# testing.net
KiCad netlist of a schematic drawn in Altium Designer
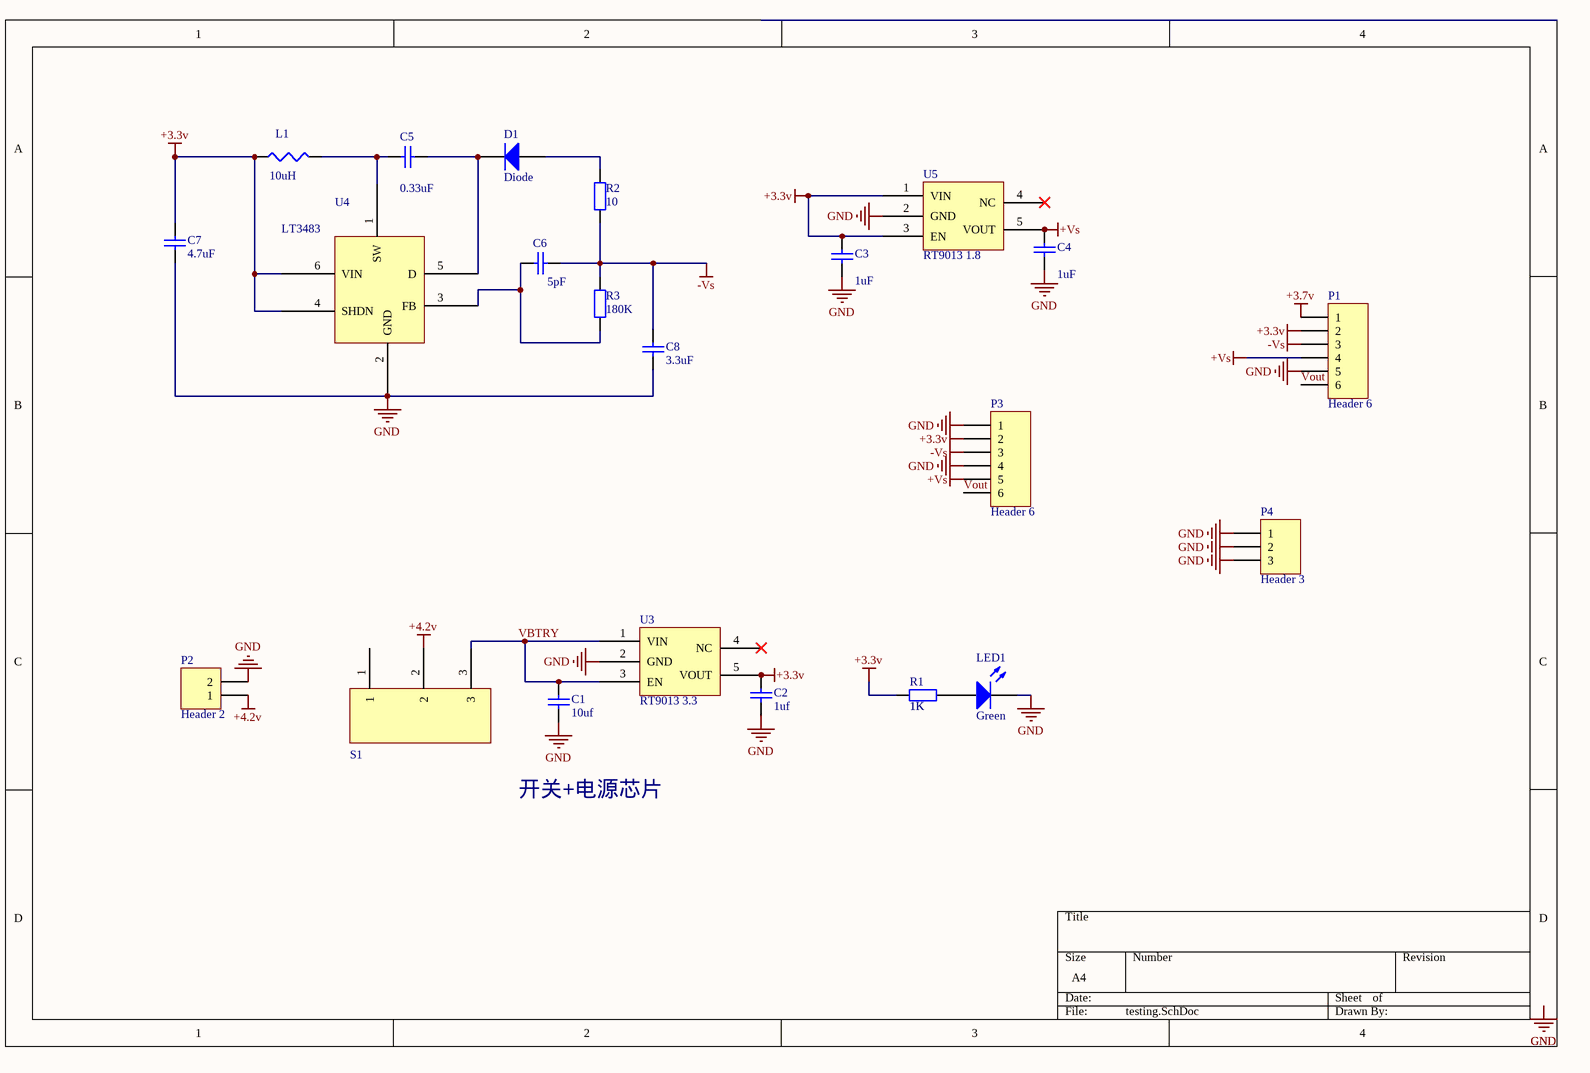
[diagram p0: testing.SchDoc]

(export (version "E")
  (design (tool "Eeschema 10.0.6"))
  (components
    (comp (ref "C1")
      (value "10uf")
      (footprint "0805")
      (description "Capacitor")
      (fields (field (name "PUBLISHER") "Altium Limited"))
      (libsource (lib "Miscellaneous Devices") (part "Cap"))
    )
    (comp (ref "C2")
      (value "1uf")
      (footprint "0805")
      (description "Capacitor")
      (fields (field (name "PUBLISHER") "Altium Limited"))
      (libsource (lib "Miscellaneous Devices") (part "Cap"))
    )
    (comp (ref "C3")
      (value "1uF")
      (footprint "0805")
      (description "Capacitor")
      (fields (field (name "PUBLISHER") "Altium Limited"))
      (libsource (lib "Miscellaneous Devices") (part "Cap"))
    )
    (comp (ref "C4")
      (value "1uF")
      (footprint "0805")
      (description "Capacitor")
      (fields (field (name "PUBLISHER") "Altium Limited"))
      (libsource (lib "Miscellaneous Devices") (part "Cap"))
    )
    (comp (ref "C5")
      (value "0.33uF")
      (footprint "0805")
      (description "Capacitor (Semiconductor SIM Model)")
      (fields (field (name "Comment") "Cap Semi") (field (name "PUBLISHER") "Altium Limited"))
      (libsource (lib "Miscellaneous Devices") (part "Cap Semi"))
    )
    (comp (ref "C6")
      (value "5pF")
      (footprint "0805")
      (description "Capacitor (Semiconductor SIM Model)")
      (fields (field (name "Comment") "Cap Semi") (field (name "PUBLISHER") "Altium Limited"))
      (libsource (lib "Miscellaneous Devices") (part "Cap Semi"))
    )
    (comp (ref "C7")
      (value "4.7uF")
      (footprint "0805")
      (description "Capacitor (Semiconductor SIM Model)")
      (fields (field (name "Comment") "Cap Semi") (field (name "PUBLISHER") "Altium Limited"))
      (libsource (lib "Miscellaneous Devices") (part "Cap Semi"))
    )
    (comp (ref "C8")
      (value "3.3uF")
      (footprint "0805")
      (description "Capacitor (Semiconductor SIM Model)")
      (fields (field (name "Comment") "Cap Semi") (field (name "PUBLISHER") "Altium Limited"))
      (libsource (lib "Miscellaneous Devices") (part "Cap Semi"))
    )
    (comp (ref "D1")
      (value "Diode")
      (footprint "D0402")
      (description "Default Diode")
      (fields (field (name "PUBLISHER") "Altium Limited"))
      (libsource (lib "Miscellaneous Devices") (part "Diode"))
    )
    (comp (ref "L1")
      (value "10uH")
      (footprint "0402 - MI")
      (description "Resistor")
      (fields (field (name "Comment") "Res3") (field (name "PUBLISHER") "Altium Limited"))
      (libsource (lib "Miscellaneous Devices") (part "Res3"))
    )
    (comp (ref "LED1")
      (value "Green")
      (footprint "0805")
      (description "Typical INFRARED GaAs LED")
      (fields (field (name "PUBLISHER") "Altium Limited"))
      (libsource (lib "Miscellaneous Devices") (part "LED0"))
    )
    (comp (ref "P1")
      (value "Header 6")
      (footprint "6P_0.5mm(FPC) - duplicate - duplicate")
      (description "Header, 6-Pin")
      (fields (field (name "PUBLISHER") "Altium Limited"))
      (libsource (lib "Miscellaneous Connectors") (part "Header 6"))
    )
    (comp (ref "P2")
      (value "Header 2")
      (footprint "HDR1X2")
      (description "Header, 2-Pin")
      (fields (field (name "PUBLISHER") "Altium Limited"))
      (libsource (lib "Miscellaneous Connectors") (part "Header 2"))
    )
    (comp (ref "P3")
      (value "Header 6")
      (footprint "HDR1X6")
      (description "Header, 6-Pin")
      (fields (field (name "PUBLISHER") "Altium Limited"))
      (libsource (lib "Miscellaneous Connectors") (part "Header 6"))
    )
    (comp (ref "P4")
      (value "Header 3")
      (footprint "HDR1X3")
      (description "Header, 3-Pin")
      (fields (field (name "PUBLISHER") "Altium Limited"))
      (libsource (lib "Miscellaneous Connectors") (part "Header 3"))
    )
    (comp (ref "R1")
      (value "1K")
      (footprint "0805")
      (description "Resistor")
      (fields (field (name "ALTIUM_VALUE") "1K") (field (name "PUBLISHER") "Altium Limited"))
      (libsource (lib "") (part "Res2_1"))
    )
    (comp (ref "R2")
      (value "10")
      (footprint "0805")
      (description "Resistor")
      (fields (field (name "PUBLISHER") "Altium Limited"))
      (libsource (lib "Miscellaneous Devices") (part "Res2"))
    )
    (comp (ref "R3")
      (value "180K")
      (footprint "0805")
      (description "Resistor")
      (fields (field (name "PUBLISHER") "Altium Limited"))
      (libsource (lib "Miscellaneous Devices") (part "Res2"))
    )
    (comp (ref "S1") (value "~") (footprint "HDR1X3") (libsource (lib "Accelerometer") (part "Switch")))
    (comp (ref "U3")
      (value "RT9013 3.3")
      (footprint "SOT23-5AM")
      (libsource (lib "CC254xPM") (part "RT9013 SOT235"))
    )
    (comp (ref "U4") (value "LT3483") (footprint "LT3843") (libsource (lib "controler") (part "LT3483")))
    (comp (ref "U5")
      (value "RT9013 1.8")
      (footprint "SC-70-5")
      (libsource (lib "CC254xPM") (part "RT9013 SOT235"))
    )
  )
  (nets
    (net (code "1") (name "+3.3v") (class "Default")
      (node (ref "C2") (pin "2") (pinfunction "2_2") (pintype "passive"))
      (node (ref "C3") (pin "2") (pinfunction "2_2") (pintype "passive"))
      (node (ref "C7") (pin "2") (pinfunction "2_2") (pintype "passive"))
      (node (ref "L1") (pin "1") (pinfunction "1_1") (pintype "passive"))
      (node (ref "P1") (pin "2") (pinfunction "2_2") (pintype "passive"))
      (node (ref "P3") (pin "2") (pinfunction "2_2") (pintype "passive"))
      (node (ref "R1") (pin "1") (pinfunction "1_1") (pintype "passive"))
      (node (ref "U3") (pin "5") (pinfunction "VOUT_5") (pintype "passive"))
      (node (ref "U4") (pin "4") (pinfunction "SHDN_4") (pintype "passive"))
      (node (ref "U4") (pin "6") (pinfunction "VIN_6") (pintype "passive"))
      (node (ref "U5") (pin "1") (pinfunction "VIN_1") (pintype "passive"))
      (node (ref "U5") (pin "3") (pinfunction "EN_3") (pintype "passive"))
    )
    (net (code "2") (name "+3.7v") (class "Default")
      (node (ref "P1") (pin "1") (pinfunction "1_1") (pintype "passive"))
    )
    (net (code "3") (name "+4.2v") (class "Default")
      (node (ref "P2") (pin "1") (pinfunction "1_1") (pintype "passive"))
      (node (ref "S1") (pin "2") (pinfunction "2_2") (pintype "passive"))
    )
    (net (code "4") (name "+Vs") (class "Default")
      (node (ref "C4") (pin "2") (pinfunction "2_2") (pintype "passive"))
      (node (ref "P1") (pin "4") (pinfunction "4_4") (pintype "passive"))
      (node (ref "P3") (pin "5") (pinfunction "5_5") (pintype "passive"))
      (node (ref "U5") (pin "5") (pinfunction "VOUT_5") (pintype "passive"))
    )
    (net (code "5") (name "-Vs") (class "Default")
      (node (ref "C6") (pin "2") (pinfunction "2_2") (pintype "passive"))
      (node (ref "C8") (pin "1") (pinfunction "1_1") (pintype "passive"))
      (node (ref "P1") (pin "3") (pinfunction "3_3") (pintype "passive"))
      (node (ref "P3") (pin "3") (pinfunction "3_3") (pintype "passive"))
      (node (ref "R2") (pin "2") (pinfunction "2_2") (pintype "passive"))
      (node (ref "R3") (pin "1") (pinfunction "1_1") (pintype "passive"))
    )
    (net (code "6") (name "/VBTRY") (class "Default")
      (node (ref "C1") (pin "2") (pinfunction "2_2") (pintype "passive"))
      (node (ref "S1") (pin "3") (pinfunction "3_3") (pintype "passive"))
      (node (ref "U3") (pin "1") (pinfunction "VIN_1") (pintype "passive"))
      (node (ref "U3") (pin "3") (pinfunction "EN_3") (pintype "passive"))
    )
    (net (code "7") (name "/Vout") (class "Default")
      (node (ref "P1") (pin "6") (pinfunction "6_6") (pintype "passive"))
      (node (ref "P3") (pin "6") (pinfunction "6_6") (pintype "passive"))
    )
    (net (code "8") (name "GND") (class "Default")
      (node (ref "C1") (pin "1") (pinfunction "1_1") (pintype "passive"))
      (node (ref "C2") (pin "1") (pinfunction "1_1") (pintype "passive"))
      (node (ref "C3") (pin "1") (pinfunction "1_1") (pintype "passive"))
      (node (ref "C4") (pin "1") (pinfunction "1_1") (pintype "passive"))
      (node (ref "C7") (pin "1") (pinfunction "1_1") (pintype "passive"))
      (node (ref "C8") (pin "2") (pinfunction "2_2") (pintype "passive"))
      (node (ref "LED1") (pin "2") (pinfunction "K_2") (pintype "passive"))
      (node (ref "P1") (pin "5") (pinfunction "5_5") (pintype "passive"))
      (node (ref "P2") (pin "2") (pinfunction "2_2") (pintype "passive"))
      (node (ref "P3") (pin "1") (pinfunction "1_1") (pintype "passive"))
      (node (ref "P3") (pin "4") (pinfunction "4_4") (pintype "passive"))
      (node (ref "P4") (pin "1") (pinfunction "1_1") (pintype "passive"))
      (node (ref "P4") (pin "2") (pinfunction "2_2") (pintype "passive"))
      (node (ref "P4") (pin "3") (pinfunction "3_3") (pintype "passive"))
      (node (ref "U3") (pin "2") (pinfunction "GND_2") (pintype "passive"))
      (node (ref "U4") (pin "2") (pinfunction "GND_2") (pintype "passive"))
      (node (ref "U5") (pin "2") (pinfunction "GND_2") (pintype "passive"))
    )
    (net (code "9") (name "Net-(D1-A)") (class "Default")
      (node (ref "D1") (pin "1") (pinfunction "A_1") (pintype "passive"))
      (node (ref "R2") (pin "1") (pinfunction "1_1") (pintype "passive"))
    )
    (net (code "10") (name "Net-(D1-K)") (class "Default")
      (node (ref "C5") (pin "2") (pinfunction "2_2") (pintype "passive"))
      (node (ref "D1") (pin "2") (pinfunction "K_2") (pintype "passive"))
      (node (ref "U4") (pin "5") (pinfunction "D_5") (pintype "passive"))
    )
    (net (code "11") (name "Net-(LED1-A)") (class "Default")
      (node (ref "LED1") (pin "1") (pinfunction "A_1") (pintype "passive"))
      (node (ref "R1") (pin "2") (pinfunction "2_2") (pintype "passive"))
    )
    (net (code "12") (name "Net-(U4-FB)") (class "Default")
      (node (ref "C6") (pin "1") (pinfunction "1_1") (pintype "passive"))
      (node (ref "R3") (pin "2") (pinfunction "2_2") (pintype "passive"))
      (node (ref "U4") (pin "3") (pinfunction "FB_3") (pintype "passive"))
    )
    (net (code "13") (name "Net-(U4-SW)") (class "Default")
      (node (ref "C5") (pin "1") (pinfunction "1_1") (pintype "passive"))
      (node (ref "L1") (pin "2") (pinfunction "2_2") (pintype "passive"))
      (node (ref "U4") (pin "1") (pinfunction "SW_1") (pintype "passive"))
    )
    (net (code "14") (name "unconnected-(S1-Pad1)") (class "Default")
      (node (ref "S1") (pin "1") (pinfunction "1_1") (pintype "passive"))
    )
    (net (code "15") (name "unconnected-(U3-NC-Pad4)") (class "Default")
      (node (ref "U3") (pin "4") (pinfunction "NC_4") (pintype "passive+no_connect"))
    )
    (net (code "16") (name "unconnected-(U5-NC-Pad4)") (class "Default")
      (node (ref "U5") (pin "4") (pinfunction "NC_4") (pintype "passive+no_connect"))
    )
  )
)
